# S52.net
KiCad netlist of a schematic drawn in Altium Designer
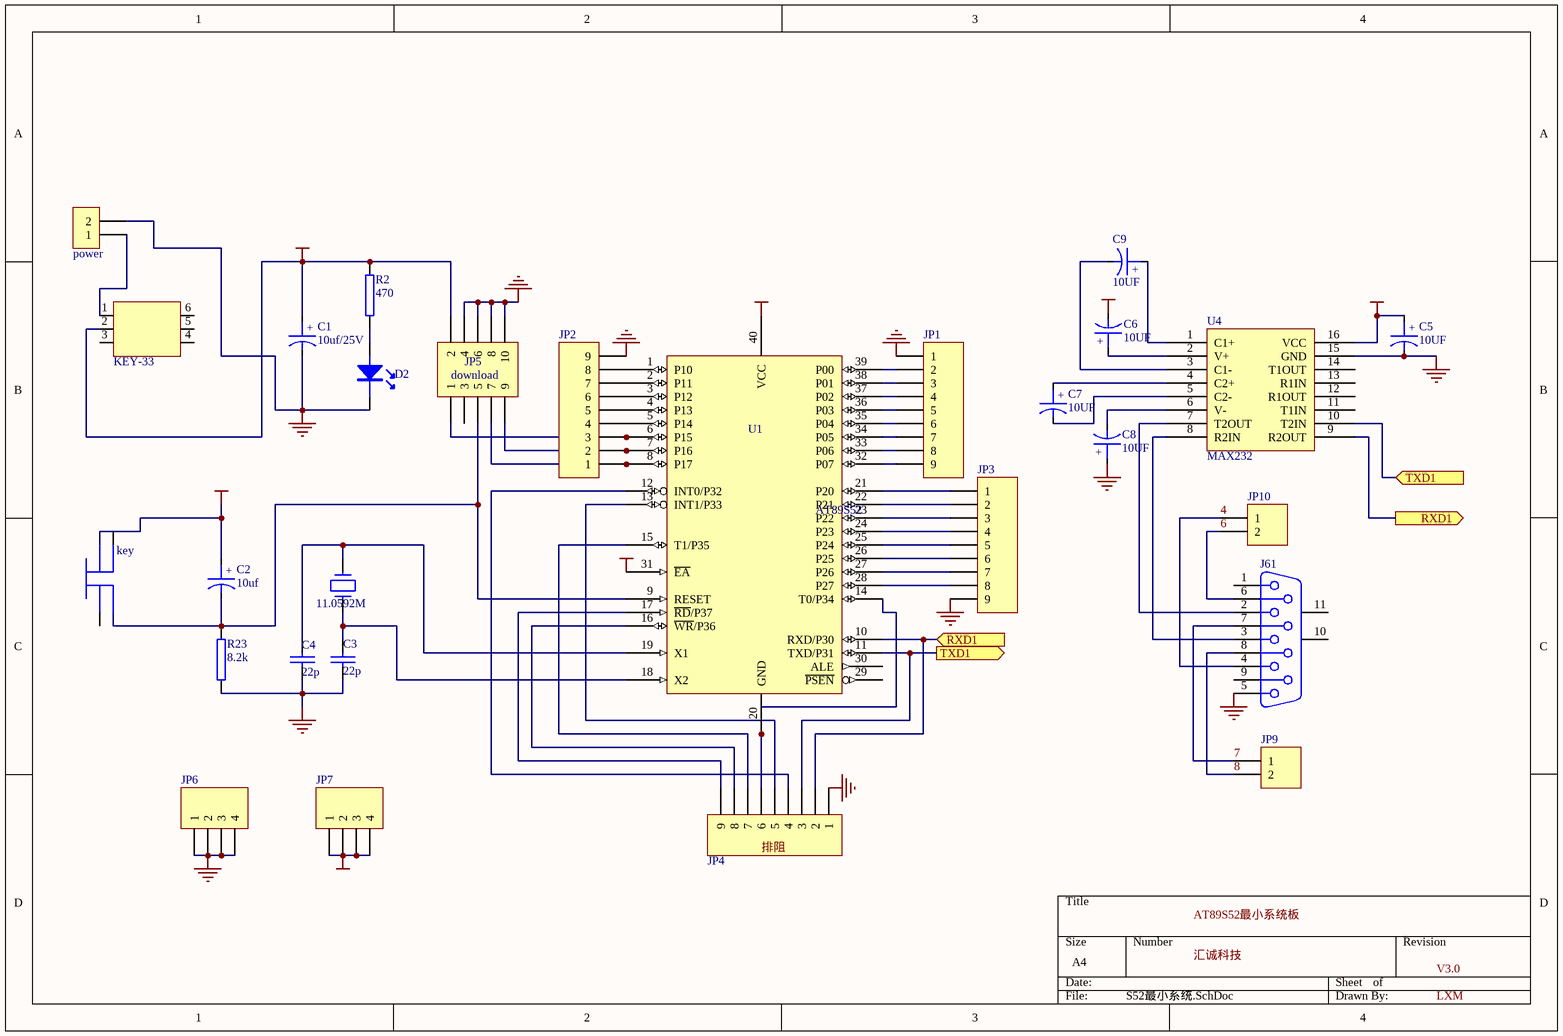
[diagram p0: S52最小系统.SchDoc]

(export (version "E")
  (design (tool "Eeschema 10.0.6"))
  (components
    (comp (ref "11") (value "power") (footprint "power1") (libsource (lib "OldCow1 (1)") (part "power")))
    (comp (ref "C1")
      (value "10uf/25V")
      (footprint "cap2")
      (description "Capacitor")
      (libsource (lib "OldCow1 (1)") (part "CAPACITOR POL"))
    )
    (comp (ref "C2")
      (value "10uf")
      (footprint "cap2")
      (description "Capacitor")
      (libsource (lib "*") (part "CAPACITOR POL"))
    )
    (comp (ref "C3")
      (value "22p")
      (footprint "RAD0.3")
      (description "Capacitor")
      (libsource (lib "*") (part "CAP"))
    )
    (comp (ref "C4")
      (value "22p")
      (footprint "RAD0.3")
      (description "Capacitor")
      (libsource (lib "*") (part "CAP"))
    )
    (comp (ref "C5")
      (value "10UF")
      (footprint "cap2")
      (description "Capacitor")
      (libsource (lib "*") (part "CAPACITOR POL"))
    )
    (comp (ref "C6")
      (value "10UF")
      (footprint "cap2")
      (description "Capacitor")
      (libsource (lib "*") (part "CAPACITOR POL"))
    )
    (comp (ref "C7")
      (value "10UF")
      (footprint "cap2")
      (description "Capacitor")
      (libsource (lib "*") (part "CAPACITOR POL"))
    )
    (comp (ref "C8")
      (value "10UF")
      (footprint "cap2")
      (description "Capacitor")
      (libsource (lib "*") (part "CAPACITOR POL"))
    )
    (comp (ref "C9")
      (value "10UF")
      (footprint "cap2")
      (description "Capacitor")
      (libsource (lib "*") (part "CAPACITOR POL"))
    )
    (comp (ref "D2") (value "LED") (footprint "LED") (libsource (lib "OldCow1 (1)") (part "LED")))
    (comp (ref "J61")
      (value "D Connector 9")
      (footprint "DSUB1.385-2H9")
      (description "Receptacle Assembly, 9 Position, Right Angle")
      (fields (field (name "PUBLISHER") "Altium Limited"))
      (libsource (lib "Miscellaneous Connectors") (part "D Connector 9"))
    )
    (comp (ref "JP1")
      (value "~")
      (footprint "HDR1X9")
      (description "Header, 9-Pin")
      (fields (field (name "PUBLISHER") "Altium Limited"))
      (libsource (lib "") (part "Header 9_1"))
    )
    (comp (ref "JP2")
      (value "~")
      (footprint "HDR1X9")
      (description "Header, 9-Pin")
      (fields (field (name "PUBLISHER") "Altium Limited"))
      (libsource (lib "Miscellaneous Connectors") (part "Header 9"))
    )
    (comp (ref "JP3")
      (value "~")
      (footprint "HDR1X9")
      (description "Header, 9-Pin")
      (fields (field (name "PUBLISHER") "Altium Limited"))
      (libsource (lib "") (part "Header 9_1"))
    )
    (comp (ref "JP4")
      (value "~")
      (footprint "HDR1X9")
      (description "Header, 9-Pin")
      (fields (field (name "PUBLISHER") "Altium Limited"))
      (libsource (lib "") (part "Header 9_2"))
    )
    (comp (ref "JP5")
      (value "download")
      (footprint "HDR2X5")
      (description "Header, 5-Pin, Dual row")
      (fields (field (name "PUBLISHER") "Altium Limited"))
      (libsource (lib "Miscellaneous Connectors") (part "Header 5X2"))
    )
    (comp (ref "JP6")
      (value "~")
      (footprint "HDR1X4")
      (description "Header, 4-Pin")
      (fields (field (name "PUBLISHER") "Altium Limited"))
      (libsource (lib "Miscellaneous Connectors") (part "Header 4"))
    )
    (comp (ref "JP7")
      (value "~")
      (footprint "HDR1X4")
      (description "Header, 4-Pin")
      (fields (field (name "PUBLISHER") "Altium Limited"))
      (libsource (lib "Miscellaneous Connectors") (part "Header 4"))
    )
    (comp (ref "JP9")
      (value "~")
      (footprint "HDR1X2")
      (description "Header, 2-Pin")
      (fields (field (name "PUBLISHER") "Altium Limited"))
      (libsource (lib "Miscellaneous Connectors") (part "Header 2"))
    )
    (comp (ref "JP10")
      (value "Header 3")
      (footprint "HDR1X2")
      (description "Header, 2-Pin")
      (fields (field (name "PUBLISHER") "Altium Limited"))
      (libsource (lib "Miscellaneous Connectors") (part "Header 2"))
    )
    (comp (ref "key") (value "KEY") (footprint "KEY-1") (libsource (lib "OldCow1 (1)") (part "KEY")))
    (comp (ref "R2") (value "470") (footprint "AXIAL0.4") (libsource (lib "*") (part "RES2")))
    (comp (ref "R23") (value "8.2k") (footprint "AXIAL0.4") (libsource (lib "*") (part "RES2")))
    (comp (ref "RT") (value "KEY-33") (footprint "KEY-2") (libsource (lib "OldCow1 (1)") (part "KEY-33")))
    (comp (ref "U1") (value "AT89S52") (footprint "AT89S52Pid") (libsource (lib "OldCow1 (2)") (part "8051")))
    (comp (ref "U4") (value "MAX232") (footprint "DIP16") (libsource (lib "*") (part "MAX232")))
    (comp (ref "Y")
      (value "11.0592M")
      (footprint "CRYSTAL")
      (description "Crystal")
      (libsource (lib "*") (part "CRYSTAL"))
    )
  )
  (nets
    (net (code "1") (name "/4") (class "Default")
      (node (ref "J61") (pin "4") (pinfunction "4_4") (pintype "passive"))
      (node (ref "JP10") (pin "1") (pinfunction "1_1") (pintype "passive"))
    )
    (net (code "2") (name "/6") (class "Default")
      (node (ref "J61") (pin "6") (pinfunction "6_6") (pintype "passive"))
      (node (ref "JP10") (pin "2") (pinfunction "2_2") (pintype "passive"))
    )
    (net (code "3") (name "/7") (class "Default")
      (node (ref "J61") (pin "7") (pinfunction "7_7") (pintype "passive"))
      (node (ref "JP9") (pin "1") (pinfunction "1_1") (pintype "passive"))
    )
    (net (code "4") (name "/8") (class "Default")
      (node (ref "J61") (pin "8") (pinfunction "8_8") (pintype "passive"))
      (node (ref "JP9") (pin "2") (pinfunction "2_2") (pintype "passive"))
    )
    (net (code "8") (name "/RXD1") (class "Default")
      (node (ref "JP4") (pin "2") (pinfunction "2_2") (pintype "passive"))
      (node (ref "U1") (pin "10") (pinfunction "RXD/P30_10") (pintype "bidirectional"))
      (node (ref "U4") (pin "9") (pinfunction "R2OUT_9") (pintype "passive"))
    )
    (net (code "9") (name "/TXD1") (class "Default")
      (node (ref "JP4") (pin "3") (pinfunction "3_3") (pintype "passive"))
      (node (ref "U1") (pin "11") (pinfunction "TXD/P31_11") (pintype "bidirectional"))
      (node (ref "U4") (pin "10") (pinfunction "T2IN_10") (pintype "passive"))
    )
    (net (code "13") (name "GND") (class "Default")
      (node (ref "11") (pin "2") (pinfunction "2_2") (pintype "passive"))
      (node (ref "C1") (pin "2") (pinfunction "2_2") (pintype "passive"))
      (node (ref "C3") (pin "2") (pinfunction "2_2") (pintype "passive"))
      (node (ref "C4") (pin "2") (pinfunction "2_2") (pintype "passive"))
      (node (ref "C5") (pin "2") (pinfunction "2_2") (pintype "passive"))
      (node (ref "C8") (pin "1") (pinfunction "1_1") (pintype "passive"))
      (node (ref "D2") (pin "2") (pinfunction "K_2") (pintype "passive"))
      (node (ref "J61") (pin "5") (pinfunction "5_5") (pintype "passive"))
      (node (ref "JP1") (pin "1") (pinfunction "1_1") (pintype "passive"))
      (node (ref "JP2") (pin "9") (pinfunction "9_9") (pintype "passive"))
      (node (ref "JP3") (pin "9") (pinfunction "9_9") (pintype "passive"))
      (node (ref "JP4") (pin "1") (pinfunction "1_1") (pintype "passive"))
      (node (ref "JP5") (pin "10") (pinfunction "10_10") (pintype "passive"))
      (node (ref "JP5") (pin "4") (pinfunction "4_4") (pintype "passive"))
      (node (ref "JP5") (pin "6") (pinfunction "6_6") (pintype "passive"))
      (node (ref "JP5") (pin "8") (pinfunction "8_8") (pintype "passive"))
      (node (ref "JP6") (pin "1") (pinfunction "1_1") (pintype "passive"))
      (node (ref "JP6") (pin "2") (pinfunction "2_2") (pintype "passive"))
      (node (ref "JP6") (pin "3") (pinfunction "3_3") (pintype "passive"))
      (node (ref "JP6") (pin "4") (pinfunction "4_4") (pintype "passive"))
      (node (ref "R23") (pin "2") (pinfunction "2_2") (pintype "passive"))
      (node (ref "U4") (pin "15") (pinfunction "GND_15") (pintype "passive"))
    )
    (net (code "14") (name "Net-(11-Pad1)") (class "Default")
      (node (ref "11") (pin "1") (pinfunction "1_1") (pintype "passive"))
      (node (ref "RT") (pin "1") (pintype "passive"))
    )
    (net (code "15") (name "Net-(D2-A)") (class "Default")
      (node (ref "D2") (pin "1") (pinfunction "A_1") (pintype "passive"))
      (node (ref "R2") (pin "2") (pinfunction "2_2") (pintype "passive"))
    )
    (net (code "16") (name "Net-(U1-GND)") (class "Default")
      (node (ref "JP4") (pin "6") (pinfunction "6_6") (pintype "passive"))
      (node (ref "U1") (pin "14") (pinfunction "T0/P34_14") (pintype "bidirectional"))
      (node (ref "U1") (pin "20") (pinfunction "GND_20") (pintype "power_in"))
    )
    (net (code "17") (name "Net-(U1-INT0{slash}P32)") (class "Default")
      (node (ref "JP4") (pin "4") (pinfunction "4_4") (pintype "passive"))
      (node (ref "U1") (pin "12") (pinfunction "INT0/P32_12") (pintype "bidirectional"))
    )
    (net (code "18") (name "Net-(U1-INT1{slash}P33)") (class "Default")
      (node (ref "JP4") (pin "5") (pinfunction "5_5") (pintype "passive"))
      (node (ref "U1") (pin "13") (pinfunction "INT1/P33_13") (pintype "bidirectional"))
    )
    (net (code "19") (name "Net-(U1-P00)") (class "Default")
      (node (ref "JP1") (pin "2") (pinfunction "2_2") (pintype "passive"))
      (node (ref "U1") (pin "39") (pinfunction "P00_39") (pintype "bidirectional"))
    )
    (net (code "20") (name "Net-(U1-P01)") (class "Default")
      (node (ref "JP1") (pin "3") (pinfunction "3_3") (pintype "passive"))
      (node (ref "U1") (pin "38") (pinfunction "P01_38") (pintype "bidirectional"))
    )
    (net (code "21") (name "Net-(U1-P02)") (class "Default")
      (node (ref "JP1") (pin "4") (pinfunction "4_4") (pintype "passive"))
      (node (ref "U1") (pin "37") (pinfunction "P02_37") (pintype "bidirectional"))
    )
    (net (code "22") (name "Net-(U1-P03)") (class "Default")
      (node (ref "JP1") (pin "5") (pinfunction "5_5") (pintype "passive"))
      (node (ref "U1") (pin "36") (pinfunction "P03_36") (pintype "bidirectional"))
    )
    (net (code "23") (name "Net-(U1-P04)") (class "Default")
      (node (ref "JP1") (pin "6") (pinfunction "6_6") (pintype "passive"))
      (node (ref "U1") (pin "35") (pinfunction "P04_35") (pintype "bidirectional"))
    )
    (net (code "24") (name "Net-(U1-P05)") (class "Default")
      (node (ref "JP1") (pin "7") (pinfunction "7_7") (pintype "passive"))
      (node (ref "U1") (pin "34") (pinfunction "P05_34") (pintype "bidirectional"))
    )
    (net (code "25") (name "Net-(U1-P06)") (class "Default")
      (node (ref "JP1") (pin "8") (pinfunction "8_8") (pintype "passive"))
      (node (ref "U1") (pin "33") (pinfunction "P06_33") (pintype "bidirectional"))
    )
    (net (code "26") (name "Net-(U1-P07)") (class "Default")
      (node (ref "JP1") (pin "9") (pinfunction "9_9") (pintype "passive"))
      (node (ref "U1") (pin "32") (pinfunction "P07_32") (pintype "bidirectional"))
    )
    (net (code "27") (name "Net-(U1-P10)") (class "Default")
      (node (ref "JP2") (pin "8") (pinfunction "8_8") (pintype "passive"))
      (node (ref "U1") (pin "1") (pinfunction "P10_1") (pintype "bidirectional"))
    )
    (net (code "28") (name "Net-(U1-P11)") (class "Default")
      (node (ref "JP2") (pin "7") (pinfunction "7_7") (pintype "passive"))
      (node (ref "U1") (pin "2") (pinfunction "P11_2") (pintype "bidirectional"))
    )
    (net (code "29") (name "Net-(U1-P12)") (class "Default")
      (node (ref "JP2") (pin "6") (pinfunction "6_6") (pintype "passive"))
      (node (ref "U1") (pin "3") (pinfunction "P12_3") (pintype "bidirectional"))
    )
    (net (code "30") (name "Net-(U1-P13)") (class "Default")
      (node (ref "JP2") (pin "5") (pinfunction "5_5") (pintype "passive"))
      (node (ref "U1") (pin "4") (pinfunction "P13_4") (pintype "bidirectional"))
    )
    (net (code "31") (name "Net-(U1-P14)") (class "Default")
      (node (ref "JP2") (pin "4") (pinfunction "4_4") (pintype "passive"))
      (node (ref "U1") (pin "5") (pinfunction "P14_5") (pintype "bidirectional"))
    )
    (net (code "32") (name "Net-(U1-P15)") (class "Default")
      (node (ref "JP2") (pin "3") (pinfunction "3_3") (pintype "passive"))
      (node (ref "JP5") (pin "1") (pinfunction "1_1") (pintype "passive"))
      (node (ref "U1") (pin "6") (pinfunction "P15_6") (pintype "bidirectional"))
    )
    (net (code "33") (name "Net-(U1-P16)") (class "Default")
      (node (ref "JP2") (pin "2") (pinfunction "2_2") (pintype "passive"))
      (node (ref "JP5") (pin "9") (pinfunction "9_9") (pintype "passive"))
      (node (ref "U1") (pin "7") (pinfunction "P16_7") (pintype "bidirectional"))
    )
    (net (code "34") (name "Net-(U1-P17)") (class "Default")
      (node (ref "JP2") (pin "1") (pinfunction "1_1") (pintype "passive"))
      (node (ref "JP5") (pin "7") (pinfunction "7_7") (pintype "passive"))
      (node (ref "U1") (pin "8") (pinfunction "P17_8") (pintype "bidirectional"))
    )
    (net (code "35") (name "Net-(U1-P20)") (class "Default")
      (node (ref "JP3") (pin "1") (pinfunction "1_1") (pintype "passive"))
      (node (ref "U1") (pin "21") (pinfunction "P20_21") (pintype "bidirectional"))
    )
    (net (code "36") (name "Net-(U1-P21)") (class "Default")
      (node (ref "JP3") (pin "2") (pinfunction "2_2") (pintype "passive"))
      (node (ref "U1") (pin "22") (pinfunction "P21_22") (pintype "bidirectional"))
    )
    (net (code "37") (name "Net-(U1-P22)") (class "Default")
      (node (ref "JP3") (pin "3") (pinfunction "3_3") (pintype "passive"))
      (node (ref "U1") (pin "23") (pinfunction "P22_23") (pintype "bidirectional"))
    )
    (net (code "38") (name "Net-(U1-P23)") (class "Default")
      (node (ref "JP3") (pin "4") (pinfunction "4_4") (pintype "passive"))
      (node (ref "U1") (pin "24") (pinfunction "P23_24") (pintype "bidirectional"))
    )
    (net (code "39") (name "Net-(U1-P24)") (class "Default")
      (node (ref "JP3") (pin "5") (pinfunction "5_5") (pintype "passive"))
      (node (ref "U1") (pin "25") (pinfunction "P24_25") (pintype "bidirectional"))
    )
    (net (code "40") (name "Net-(U1-P25)") (class "Default")
      (node (ref "JP3") (pin "6") (pinfunction "6_6") (pintype "passive"))
      (node (ref "U1") (pin "26") (pinfunction "P25_26") (pintype "bidirectional"))
    )
    (net (code "41") (name "Net-(U1-P26)") (class "Default")
      (node (ref "JP3") (pin "7") (pinfunction "7_7") (pintype "passive"))
      (node (ref "U1") (pin "27") (pinfunction "P26_27") (pintype "bidirectional"))
    )
    (net (code "42") (name "Net-(U1-P27)") (class "Default")
      (node (ref "JP3") (pin "8") (pinfunction "8_8") (pintype "passive"))
      (node (ref "U1") (pin "28") (pinfunction "P27_28") (pintype "bidirectional"))
    )
    (net (code "43") (name "Net-(U1-RESET)") (class "Default")
      (node (ref "C2") (pin "2") (pinfunction "2_2") (pintype "passive"))
      (node (ref "JP5") (pin "5") (pinfunction "5_5") (pintype "passive"))
      (node (ref "R23") (pin "1") (pinfunction "1_1") (pintype "passive"))
      (node (ref "U1") (pin "9") (pinfunction "RESET_9") (pintype "input"))
      (node (ref "key") (pin "2") (pinfunction "2_2") (pintype "passive"))
    )
    (net (code "44") (name "Net-(U1-T1{slash}P35)") (class "Default")
      (node (ref "JP4") (pin "7") (pinfunction "7_7") (pintype "passive"))
      (node (ref "U1") (pin "15") (pinfunction "T1/P35_15") (pintype "bidirectional"))
    )
    (net (code "45") (name "Net-(U1-X1)") (class "Default")
      (node (ref "C4") (pin "1") (pinfunction "1_1") (pintype "passive"))
      (node (ref "U1") (pin "19") (pinfunction "X1_19") (pintype "input"))
      (node (ref "Y") (pin "1") (pinfunction "1_1") (pintype "passive"))
    )
    (net (code "46") (name "Net-(U1-X2)") (class "Default")
      (node (ref "C3") (pin "1") (pinfunction "1_1") (pintype "passive"))
      (node (ref "U1") (pin "18") (pinfunction "X2_18") (pintype "input"))
      (node (ref "Y") (pin "2") (pinfunction "2_2") (pintype "passive"))
    )
    (net (code "47") (name "Net-(U1-~{RD}{slash}P37)") (class "Default")
      (node (ref "JP4") (pin "9") (pinfunction "9_9") (pintype "passive"))
      (node (ref "U1") (pin "17") (pinfunction "~{RD}/P37_17") (pintype "input"))
    )
    (net (code "48") (name "Net-(U1-~{WR}{slash}P36)") (class "Default")
      (node (ref "JP4") (pin "8") (pinfunction "8_8") (pintype "passive"))
      (node (ref "U1") (pin "16") (pinfunction "~{WR}/P36_16") (pintype "bidirectional"))
    )
    (net (code "49") (name "Net-(U4-C1+)") (class "Default")
      (node (ref "C9") (pin "1") (pinfunction "1_1") (pintype "passive"))
      (node (ref "U4") (pin "1") (pinfunction "C1+_1") (pintype "passive"))
    )
    (net (code "50") (name "Net-(U4-C1-)") (class "Default")
      (node (ref "C9") (pin "2") (pinfunction "2_2") (pintype "passive"))
      (node (ref "U4") (pin "3") (pinfunction "C1-_3") (pintype "passive"))
    )
    (net (code "51") (name "Net-(U4-C2+)") (class "Default")
      (node (ref "C7") (pin "1") (pinfunction "1_1") (pintype "passive"))
      (node (ref "U4") (pin "4") (pinfunction "C2+_4") (pintype "passive"))
    )
    (net (code "52") (name "Net-(U4-C2-)") (class "Default")
      (node (ref "C7") (pin "2") (pinfunction "2_2") (pintype "passive"))
      (node (ref "U4") (pin "5") (pinfunction "C2-_5") (pintype "passive"))
    )
    (net (code "53") (name "Net-(U4-R2IN)") (class "Default")
      (node (ref "J61") (pin "3") (pinfunction "3_3") (pintype "passive"))
      (node (ref "U4") (pin "8") (pinfunction "R2IN_8") (pintype "passive"))
    )
    (net (code "54") (name "Net-(U4-T2OUT)") (class "Default")
      (node (ref "J61") (pin "2") (pinfunction "2_2") (pintype "passive"))
      (node (ref "U4") (pin "7") (pinfunction "T2OUT_7") (pintype "passive"))
    )
    (net (code "55") (name "Net-(U4-V+)") (class "Default")
      (node (ref "C6") (pin "1") (pinfunction "1_1") (pintype "passive"))
      (node (ref "U4") (pin "2") (pinfunction "V+_2") (pintype "passive"))
    )
    (net (code "56") (name "Net-(U4-V-)") (class "Default")
      (node (ref "C8") (pin "2") (pinfunction "2_2") (pintype "passive"))
      (node (ref "U4") (pin "6") (pinfunction "V-_6") (pintype "passive"))
    )
    (net (code "57") (name "VCC") (class "Default")
      (node (ref "C1") (pin "1") (pinfunction "1_1") (pintype "passive"))
      (node (ref "C2") (pin "1") (pinfunction "1_1") (pintype "passive"))
      (node (ref "C5") (pin "1") (pinfunction "1_1") (pintype "passive"))
      (node (ref "C6") (pin "2") (pinfunction "2_2") (pintype "passive"))
      (node (ref "JP5") (pin "2") (pinfunction "2_2") (pintype "passive"))
      (node (ref "JP7") (pin "1") (pinfunction "1_1") (pintype "passive"))
      (node (ref "JP7") (pin "2") (pinfunction "2_2") (pintype "passive"))
      (node (ref "JP7") (pin "3") (pinfunction "3_3") (pintype "passive"))
      (node (ref "JP7") (pin "4") (pinfunction "4_4") (pintype "passive"))
      (node (ref "R2") (pin "1") (pinfunction "1_1") (pintype "passive"))
      (node (ref "RT") (pin "2") (pintype "passive"))
      (node (ref "U1") (pin "31") (pinfunction "~{EA}_31") (pintype "input"))
      (node (ref "U1") (pin "40") (pinfunction "VCC_40") (pintype "power_in"))
      (node (ref "U4") (pin "16") (pinfunction "VCC_16") (pintype "passive"))
      (node (ref "key") (pin "1") (pinfunction "1_1") (pintype "passive"))
    )
    (net (code "58") (name "unconnected-(J61-MH1-Pad10)") (class "Default")
      (node (ref "J61") (pin "10") (pinfunction "MH1_10") (pintype "passive"))
    )
    (net (code "59") (name "unconnected-(J61-MH2-Pad11)") (class "Default")
      (node (ref "J61") (pin "11") (pinfunction "MH2_11") (pintype "passive"))
    )
    (net (code "60") (name "unconnected-(J61-Pad1)") (class "Default")
      (node (ref "J61") (pin "1") (pinfunction "1_1") (pintype "passive"))
    )
    (net (code "61") (name "unconnected-(J61-Pad9)") (class "Default")
      (node (ref "J61") (pin "9") (pinfunction "9_9") (pintype "passive"))
    )
    (net (code "62") (name "unconnected-(JP5-Pad3)") (class "Default")
      (node (ref "JP5") (pin "3") (pinfunction "3_3") (pintype "passive"))
    )
    (net (code "63") (name "unconnected-(RT-Pad3)") (class "Default")
      (node (ref "RT") (pin "3") (pintype "passive"))
    )
    (net (code "64") (name "unconnected-(RT-Pad4)") (class "Default")
      (node (ref "RT") (pin "4") (pintype "passive"))
    )
    (net (code "65") (name "unconnected-(RT-Pad5)") (class "Default")
      (node (ref "RT") (pin "5") (pintype "passive"))
    )
    (net (code "66") (name "unconnected-(RT-Pad6)") (class "Default")
      (node (ref "RT") (pin "6") (pintype "passive"))
    )
    (net (code "67") (name "unconnected-(U1-ALE-Pad30)") (class "Default")
      (node (ref "U1") (pin "30") (pinfunction "ALE_30") (pintype "output"))
    )
    (net (code "68") (name "unconnected-(U1-~{PSEN}-Pad29)") (class "Default")
      (node (ref "U1") (pin "29") (pinfunction "~{PSEN}_29") (pintype "output"))
    )
    (net (code "69") (name "unconnected-(U4-R1IN-Pad13)") (class "Default")
      (node (ref "U4") (pin "13") (pinfunction "R1IN_13") (pintype "passive"))
    )
    (net (code "70") (name "unconnected-(U4-R1OUT-Pad12)") (class "Default")
      (node (ref "U4") (pin "12") (pinfunction "R1OUT_12") (pintype "passive"))
    )
    (net (code "71") (name "unconnected-(U4-T1IN-Pad11)") (class "Default")
      (node (ref "U4") (pin "11") (pinfunction "T1IN_11") (pintype "passive"))
    )
    (net (code "72") (name "unconnected-(U4-T1OUT-Pad14)") (class "Default")
      (node (ref "U4") (pin "14") (pinfunction "T1OUT_14") (pintype "passive"))
    )
    (net (code "73") (name "unconnected-(key-Pad0)") (class "Default")
      (node (ref "key") (pin "0") (pinfunction "0_0") (pintype "passive"))
    )
    (net (code "74") (name "unconnected-(key-Pad3)") (class "Default")
      (node (ref "key") (pin "3") (pinfunction "3_3") (pintype "passive"))
    )
  )
)
